# Power.net
KiCad netlist of a schematic drawn in Altium Designer
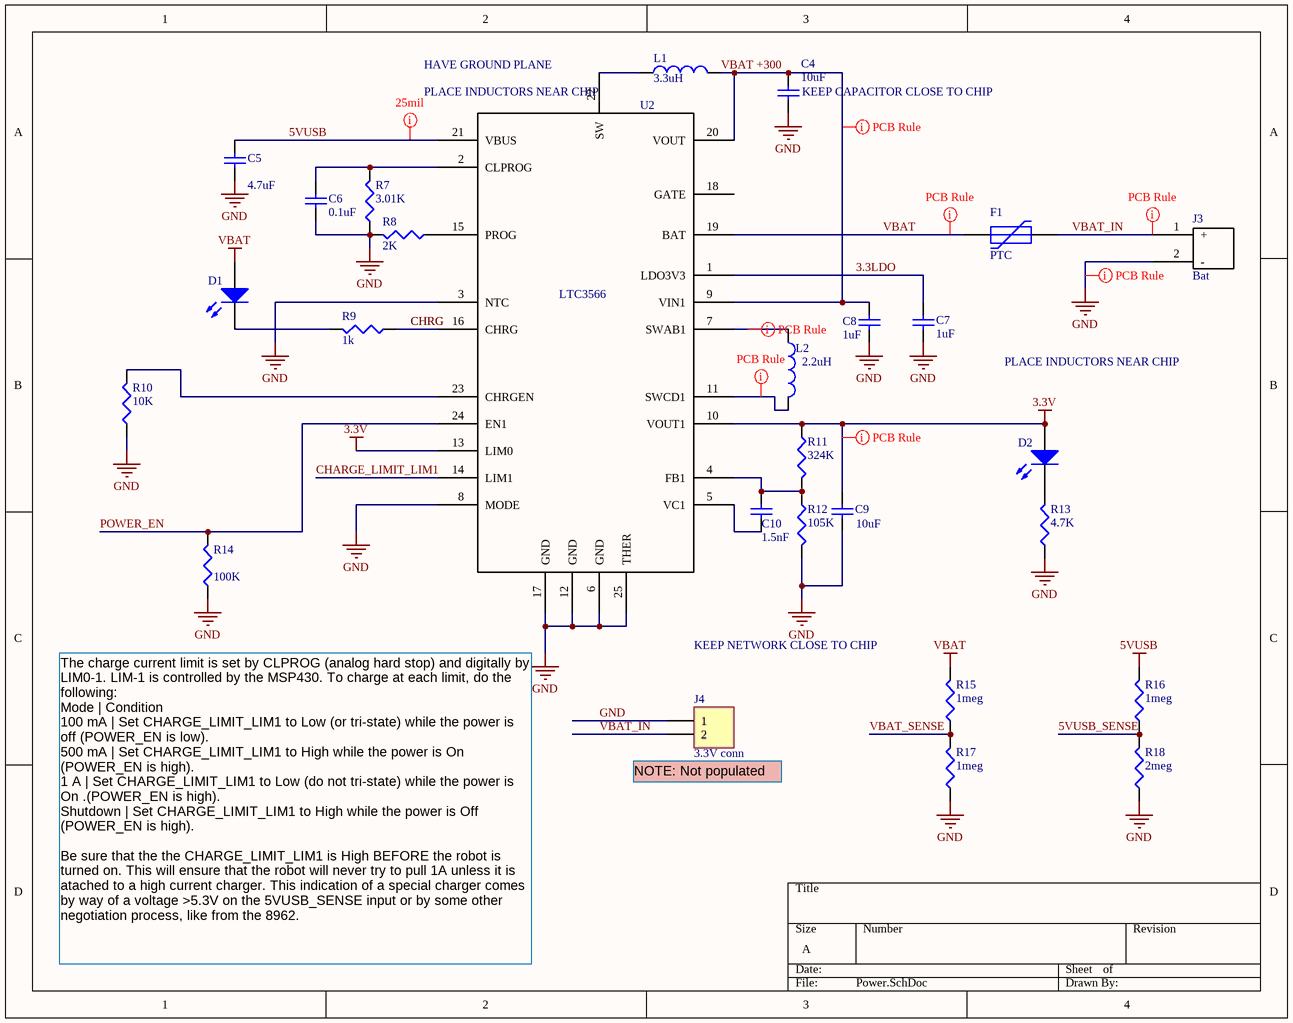
[diagram p0: Power.SchDoc]

(export (version "E")
  (design (tool "Eeschema 10.0.6"))
  (components
    (comp (ref "C4")
      (value "10uF")
      (footprint "CAPC1608L")
      (description "Capacitor")
      (fields (field (name "Comment") "Cap") (field (name "PUBLISHER") "Altium Limited"))
      (libsource (lib "Miscellaneous Devices") (part "Cap"))
    )
    (comp (ref "C5")
      (value "4.7uF")
      (footprint "CAPC1608L")
      (description "Capacitor (Semiconductor SIM Model)")
      (fields (field (name "Comment") "Cap Semi") (field (name "PUBLISHER") "Altium Limited"))
      (libsource (lib "Miscellaneous Devices") (part "Cap Semi"))
    )
    (comp (ref "C6")
      (value "0.1uF")
      (footprint "CAPC1005L")
      (description "Capacitor")
      (fields (field (name "Comment") "Cap") (field (name "PUBLISHER") "Altium Limited"))
      (libsource (lib "Miscellaneous Devices") (part "Cap"))
    )
    (comp (ref "C7")
      (value "1uF")
      (footprint "CAPC1608L")
      (description "Capacitor")
      (fields (field (name "Comment") "Cap") (field (name "PUBLISHER") "Altium Limited"))
      (libsource (lib "Miscellaneous Devices") (part "Cap"))
    )
    (comp (ref "C8")
      (value "1uF")
      (footprint "CAPC1608L")
      (description "Capacitor")
      (fields (field (name "Comment") "Cap") (field (name "PUBLISHER") "Altium Limited"))
      (libsource (lib "Miscellaneous Devices") (part "Cap"))
    )
    (comp (ref "C9")
      (value "10uF")
      (footprint "CAPC1608L")
      (description "Capacitor")
      (fields (field (name "Comment") "Cap") (field (name "PUBLISHER") "Altium Limited"))
      (libsource (lib "Miscellaneous Devices") (part "Cap"))
    )
    (comp (ref "C10")
      (value "1.5nF")
      (footprint "CAPC1005L")
      (description "Capacitor")
      (fields (field (name "Comment") "Cap") (field (name "PUBLISHER") "Altium Limited"))
      (libsource (lib "Miscellaneous Devices") (part "Cap"))
    )
    (comp (ref "D1")
      (value "Charge")
      (footprint "INDC2012L")
      (description "Typical RED, GREEN, YELLOW, AMBER GaAs LED")
      (fields (field (name "PUBLISHER") "Altium Limited"))
      (libsource (lib "Miscellaneous Devices") (part "LED2"))
    )
    (comp (ref "D2")
      (value "Power")
      (footprint "INDC2012L")
      (description "Typical RED, GREEN, YELLOW, AMBER GaAs LED")
      (fields (field (name "PUBLISHER") "Altium Limited"))
      (libsource (lib "Miscellaneous Devices") (part "LED2"))
    )
    (comp (ref "F1")
      (value "PTC")
      (footprint "ERJ8G-1206")
      (description "Fuse")
      (fields (field (name "PUBLISHER") "Altium Limited"))
      (libsource (lib "mrone") (part "PTC_FUSE"))
    )
    (comp (ref "J3")
      (value "Bat")
      (footprint "BatteryConnJST")
      (libsource (lib "mrone") (part "BatteryConnJST"))
    )
    (comp (ref "J4")
      (value "3.3V conn")
      (footprint "HDR1X2")
      (description "Header, 2-Pin")
      (fields (field (name "PUBLISHER") "Altium Limited"))
      (libsource (lib "Miscellaneous Connectors") (part "Header 2"))
    )
    (comp (ref "L1") (value "3.3uH") (footprint "IndPow") (libsource (lib "mrone") (part "Inductor")))
    (comp (ref "L2") (value "2.2uH") (footprint "IndPow") (libsource (lib "mrone") (part "Inductor")))
    (comp (ref "R7")
      (value "3.01K")
      (footprint "RESC1608L")
      (description "Resistor")
      (fields (field (name "Comment") "Res3") (field (name "PUBLISHER") "Altium Limited"))
      (libsource (lib "Miscellaneous Devices") (part "Res3"))
    )
    (comp (ref "R8")
      (value "2K")
      (footprint "RESC1608L")
      (description "Resistor")
      (fields (field (name "Comment") "Res3") (field (name "PUBLISHER") "Altium Limited"))
      (libsource (lib "Miscellaneous Devices") (part "Res3"))
    )
    (comp (ref "R9")
      (value "1k")
      (footprint "RESC1608L")
      (description "Resistor")
      (fields (field (name "Comment") "Res3") (field (name "PUBLISHER") "Altium Limited"))
      (libsource (lib "Miscellaneous Devices") (part "Res3"))
    )
    (comp (ref "R10")
      (value "10K")
      (footprint "RESC1608L")
      (description "Resistor")
      (fields (field (name "Comment") "Res3") (field (name "PUBLISHER") "Altium Limited"))
      (libsource (lib "Miscellaneous Devices") (part "Res3"))
    )
    (comp (ref "R11")
      (value "324K")
      (footprint "RESC1608L")
      (description "Resistor")
      (fields (field (name "Comment") "Res3") (field (name "PUBLISHER") "Altium Limited"))
      (libsource (lib "Miscellaneous Devices") (part "Res3"))
    )
    (comp (ref "R12")
      (value "105K")
      (footprint "RESC1608L")
      (description "Resistor")
      (fields (field (name "Comment") "Res3") (field (name "PUBLISHER") "Altium Limited"))
      (libsource (lib "Miscellaneous Devices") (part "Res3"))
    )
    (comp (ref "R13")
      (value "4.7K")
      (footprint "RESC1608L")
      (description "Resistor")
      (fields (field (name "Comment") "Res3") (field (name "PUBLISHER") "Altium Limited"))
      (libsource (lib "Miscellaneous Devices") (part "Res3"))
    )
    (comp (ref "R14")
      (value "100K")
      (footprint "RESC1608L")
      (description "Resistor")
      (fields (field (name "Comment") "Res3") (field (name "PUBLISHER") "Altium Limited"))
      (libsource (lib "Miscellaneous Devices") (part "Res3"))
    )
    (comp (ref "R15")
      (value "1meg")
      (footprint "RESC1608L")
      (description "Resistor")
      (fields (field (name "Comment") "Res3") (field (name "PUBLISHER") "Altium Limited"))
      (libsource (lib "Miscellaneous Devices") (part "Res3"))
    )
    (comp (ref "R16")
      (value "1meg")
      (footprint "RESC1608L")
      (description "Resistor")
      (fields (field (name "Comment") "Res3") (field (name "PUBLISHER") "Altium Limited"))
      (libsource (lib "Miscellaneous Devices") (part "Res3"))
    )
    (comp (ref "R17")
      (value "1meg")
      (footprint "RESC1608L")
      (description "Resistor")
      (fields (field (name "Comment") "Res3") (field (name "PUBLISHER") "Altium Limited"))
      (libsource (lib "Miscellaneous Devices") (part "Res3"))
    )
    (comp (ref "R18")
      (value "2meg")
      (footprint "RESC1608L")
      (description "Resistor")
      (fields (field (name "Comment") "Res3") (field (name "PUBLISHER") "Altium Limited"))
      (libsource (lib "Miscellaneous Devices") (part "Res3"))
    )
    (comp (ref "U2")
      (value "LTC3566")
      (footprint "QFN-24")
      (libsource (lib "Schematic Components") (part "LTC3566"))
    )
  )
  (nets
    (net (code "1") (name "/3.3LDO") (class "Default")
      (node (ref "C7") (pin "1") (pinfunction "1_1") (pintype "passive"))
      (node (ref "U2") (pin "1") (pinfunction "LDO3V3_1") (pintype "passive"))
    )
    (net (code "2") (name "/5VUSB_SENSE") (class "Default")
      (node (ref "R16") (pin "1") (pinfunction "1_1") (pintype "passive"))
      (node (ref "R18") (pin "2") (pinfunction "2_2") (pintype "passive"))
    )
    (net (code "3") (name "/CHARGE_LIMIT_LIM1") (class "Default")
      (node (ref "U2") (pin "14") (pinfunction "LIM1_14") (pintype "passive"))
    )
    (net (code "4") (name "/CHRG") (class "Default")
      (node (ref "R9") (pin "1") (pinfunction "1_1") (pintype "passive"))
      (node (ref "U2") (pin "16") (pinfunction "CHRG_16") (pintype "passive"))
    )
    (net (code "5") (name "/POWER_EN") (class "Default")
      (node (ref "R14") (pin "2") (pinfunction "2_2") (pintype "passive"))
      (node (ref "U2") (pin "24") (pinfunction "EN1_24") (pintype "passive"))
    )
    (net (code "6") (name "/VBAT +300") (class "Default")
      (node (ref "C4") (pin "2") (pinfunction "2_2") (pintype "passive"))
      (node (ref "C8") (pin "1") (pinfunction "1_1") (pintype "passive"))
      (node (ref "L1") (pin "2") (pinfunction "2_2") (pintype "passive"))
      (node (ref "U2") (pin "20") (pinfunction "VOUT_20") (pintype "passive"))
      (node (ref "U2") (pin "9") (pinfunction "VIN1_9") (pintype "passive"))
    )
    (net (code "7") (name "/VBAT_IN") (class "Default")
      (node (ref "F1") (pin "2") (pinfunction "2_2") (pintype "passive"))
      (node (ref "J3") (pin "1") (pinfunction "+_1") (pintype "passive"))
      (node (ref "J4") (pin "2") (pinfunction "2_2") (pintype "passive"))
    )
    (net (code "8") (name "/VBAT_SENSE") (class "Default")
      (node (ref "R15") (pin "1") (pinfunction "1_1") (pintype "passive"))
      (node (ref "R17") (pin "2") (pinfunction "2_2") (pintype "passive"))
    )
    (net (code "9") (name "3.3V") (class "Default")
      (node (ref "C9") (pin "2") (pinfunction "2_2") (pintype "passive"))
      (node (ref "D2") (pin "1") (pinfunction "A_1") (pintype "passive"))
      (node (ref "R11") (pin "1") (pinfunction "1_1") (pintype "passive"))
      (node (ref "U2") (pin "10") (pinfunction "VOUT1_10") (pintype "passive"))
      (node (ref "U2") (pin "13") (pinfunction "LIM0_13") (pintype "passive"))
    )
    (net (code "10") (name "5VUSB") (class "Default")
      (node (ref "C5") (pin "2") (pinfunction "2_2") (pintype "passive"))
      (node (ref "R16") (pin "2") (pinfunction "2_2") (pintype "passive"))
      (node (ref "U2") (pin "21") (pinfunction "VBUS_21") (pintype "passive"))
    )
    (net (code "11") (name "GND") (class "Default")
      (node (ref "C4") (pin "1") (pinfunction "1_1") (pintype "passive"))
      (node (ref "C5") (pin "1") (pinfunction "1_1") (pintype "passive"))
      (node (ref "C6") (pin "1") (pinfunction "1_1") (pintype "passive"))
      (node (ref "C7") (pin "2") (pinfunction "2_2") (pintype "passive"))
      (node (ref "C8") (pin "2") (pinfunction "2_2") (pintype "passive"))
      (node (ref "C9") (pin "1") (pinfunction "1_1") (pintype "passive"))
      (node (ref "J3") (pin "2") (pinfunction "-_2") (pintype "passive"))
      (node (ref "J4") (pin "1") (pinfunction "1_1") (pintype "passive"))
      (node (ref "R10") (pin "1") (pinfunction "1_1") (pintype "passive"))
      (node (ref "R12") (pin "2") (pinfunction "2_2") (pintype "passive"))
      (node (ref "R13") (pin "1") (pinfunction "1_1") (pintype "passive"))
      (node (ref "R14") (pin "1") (pinfunction "1_1") (pintype "passive"))
      (node (ref "R17") (pin "1") (pinfunction "1_1") (pintype "passive"))
      (node (ref "R18") (pin "1") (pinfunction "1_1") (pintype "passive"))
      (node (ref "R7") (pin "1") (pinfunction "1_1") (pintype "passive"))
      (node (ref "R8") (pin "2") (pinfunction "2_2") (pintype "passive"))
      (node (ref "U2") (pin "12") (pinfunction "GND_12") (pintype "passive"))
      (node (ref "U2") (pin "17") (pinfunction "GND_17") (pintype "passive"))
      (node (ref "U2") (pin "25") (pinfunction "THER_25") (pintype "passive"))
      (node (ref "U2") (pin "3") (pinfunction "NTC_3") (pintype "passive"))
      (node (ref "U2") (pin "6") (pinfunction "GND_6") (pintype "passive"))
      (node (ref "U2") (pin "8") (pinfunction "MODE_8") (pintype "passive"))
    )
    (net (code "12") (name "Net-(D1-K)") (class "Default")
      (node (ref "D1") (pin "2") (pinfunction "K_2") (pintype "passive"))
      (node (ref "R9") (pin "2") (pinfunction "2_2") (pintype "passive"))
    )
    (net (code "13") (name "Net-(D2-K)") (class "Default")
      (node (ref "D2") (pin "2") (pinfunction "K_2") (pintype "passive"))
      (node (ref "R13") (pin "2") (pinfunction "2_2") (pintype "passive"))
    )
    (net (code "14") (name "Net-(U2-CHRGEN)") (class "Default")
      (node (ref "R10") (pin "2") (pinfunction "2_2") (pintype "passive"))
      (node (ref "U2") (pin "23") (pinfunction "CHRGEN_23") (pintype "passive"))
    )
    (net (code "15") (name "Net-(U2-CLPROG)") (class "Default")
      (node (ref "C6") (pin "2") (pinfunction "2_2") (pintype "passive"))
      (node (ref "R7") (pin "2") (pinfunction "2_2") (pintype "passive"))
      (node (ref "U2") (pin "2") (pinfunction "CLPROG_2") (pintype "passive"))
    )
    (net (code "16") (name "Net-(U2-FB1)") (class "Default")
      (node (ref "C10") (pin "1") (pinfunction "1_1") (pintype "passive"))
      (node (ref "R11") (pin "2") (pinfunction "2_2") (pintype "passive"))
      (node (ref "R12") (pin "1") (pinfunction "1_1") (pintype "passive"))
      (node (ref "U2") (pin "4") (pinfunction "FB1_4") (pintype "passive"))
    )
    (net (code "17") (name "Net-(U2-PROG)") (class "Default")
      (node (ref "R8") (pin "1") (pinfunction "1_1") (pintype "passive"))
      (node (ref "U2") (pin "15") (pinfunction "PROG_15") (pintype "passive"))
    )
    (net (code "18") (name "Net-(U2-SW)") (class "Default")
      (node (ref "L1") (pin "1") (pinfunction "1_1") (pintype "passive"))
      (node (ref "U2") (pin "22") (pinfunction "SW_22") (pintype "passive"))
    )
    (net (code "19") (name "Net-(U2-SWAB1)") (class "Default")
      (node (ref "L2") (pin "1") (pinfunction "1_1") (pintype "passive"))
      (node (ref "U2") (pin "7") (pinfunction "SWAB1_7") (pintype "passive"))
    )
    (net (code "20") (name "Net-(U2-SWCD1)") (class "Default")
      (node (ref "L2") (pin "2") (pinfunction "2_2") (pintype "passive"))
      (node (ref "U2") (pin "11") (pinfunction "SWCD1_11") (pintype "passive"))
    )
    (net (code "21") (name "Net-(U2-VC1)") (class "Default")
      (node (ref "C10") (pin "2") (pinfunction "2_2") (pintype "passive"))
      (node (ref "U2") (pin "5") (pinfunction "VC1_5") (pintype "passive"))
    )
    (net (code "22") (name "VBAT") (class "Default")
      (node (ref "D1") (pin "1") (pinfunction "A_1") (pintype "passive"))
      (node (ref "F1") (pin "1") (pinfunction "1_1") (pintype "passive"))
      (node (ref "R15") (pin "2") (pinfunction "2_2") (pintype "passive"))
      (node (ref "U2") (pin "19") (pinfunction "BAT_19") (pintype "passive"))
    )
    (net (code "23") (name "unconnected-(U2-GATE-Pad18)") (class "Default")
      (node (ref "U2") (pin "18") (pinfunction "GATE_18") (pintype "passive"))
    )
  )
)
